# TSAL.net
KiCad netlist of a schematic drawn in EasyEDA Pro
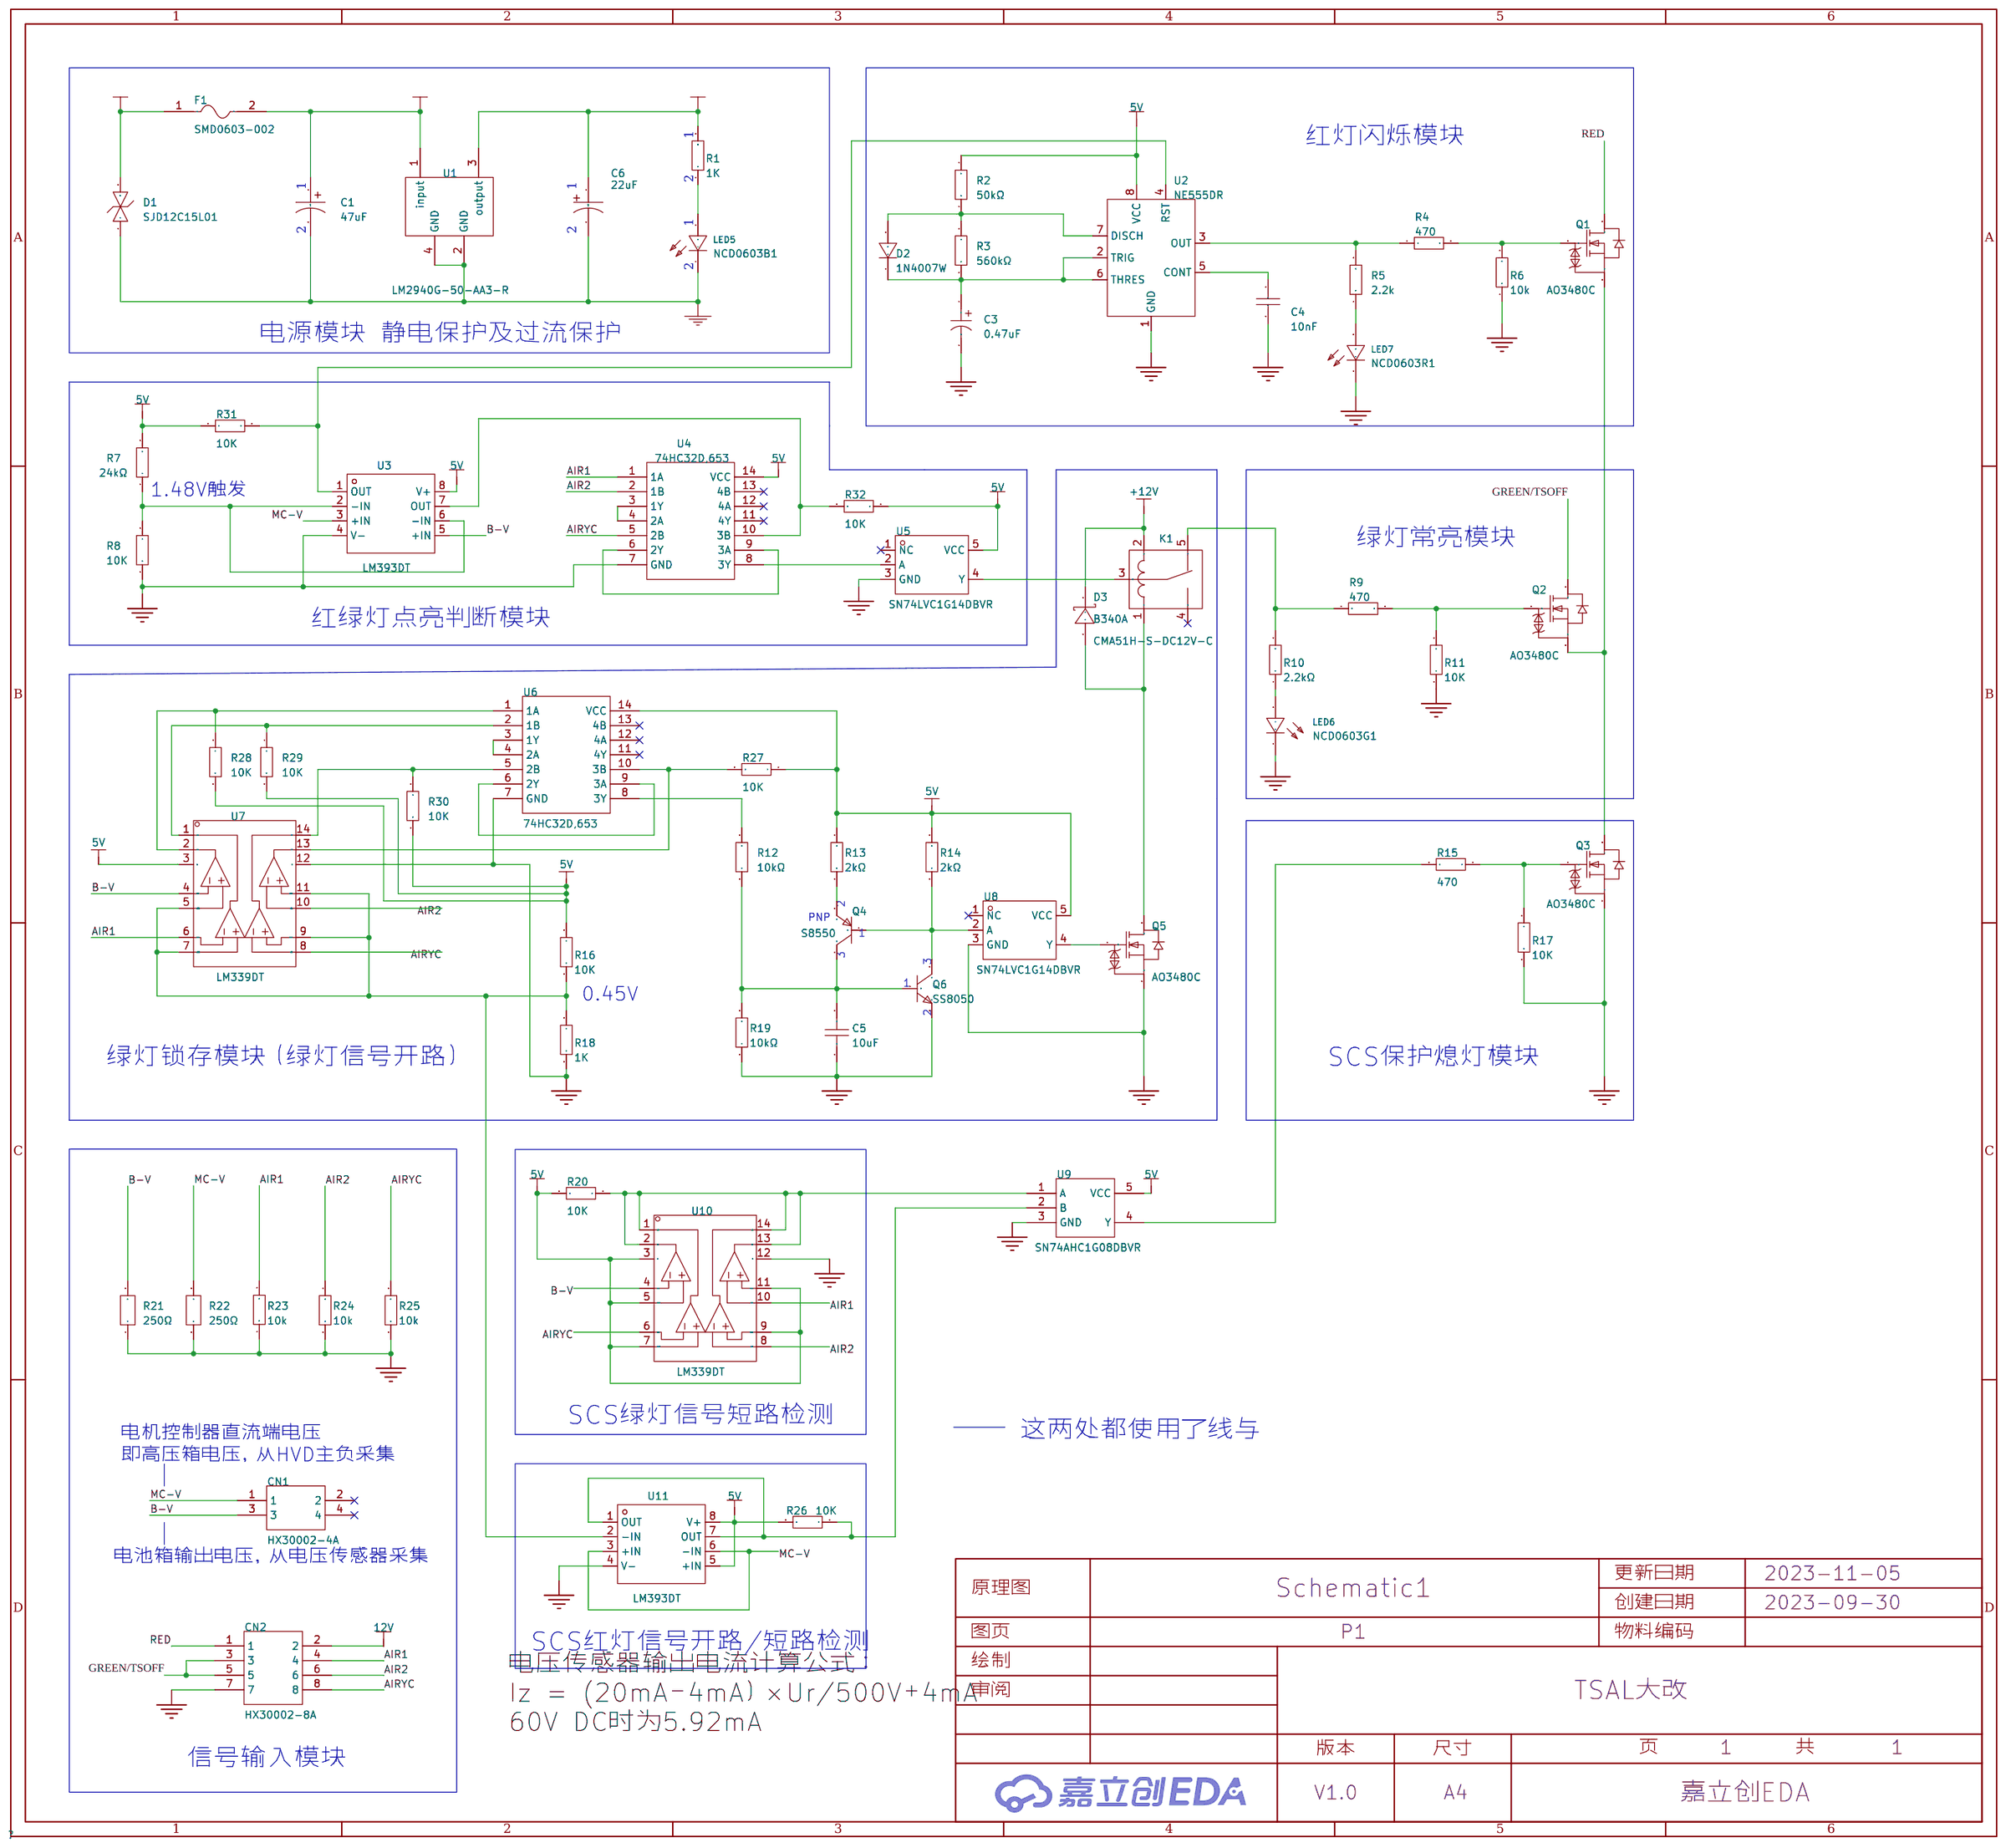
[diagram p0: schematic sheet]

(export (version "E")
  (design (tool "Eeschema 10.0.6"))
  (components
    (comp (ref "C1")
      (value "47uF")
      (footprint "easyedapro:CAP-SMD_BD8.0-L8.3-W8.3-FD")
      (description "容值:47uF;精度:±20%;额定电压:63V;")
      (fields (field (name "Manufacturer Part") "HBW470M1JTR-0810") (field (name "Manufacturer") "lelon(立隆)"))
      (libsource (lib "easyedapro") (part "HBW470M1JTR-0810"))
    )
    (comp (ref "C3")
      (value "0.47uF")
      (footprint "easyedapro:CAP-SMD_L3.2-W1.6-FD-1")
      (description "容值:470nF;精度:±10%;额定电压:35V;")
      (fields
        (field (name "Manufacturer Part") "CA45A-A-35V-0.47UF-K")
        (field (name "Manufacturer") "CEC(振华新云)")
      )
      (libsource (lib "easyedapro") (part "CA45A-A-35V-0.47UF-K"))
    )
    (comp (ref "C4")
      (value "10nF")
      (footprint "easyedapro:C0603")
      (description "容值:10nF;精度:±10%;额定电压:50V;材质(温度系数):X7R;")
      (fields (field (name "Manufacturer Part") "0603B103K500NT") (field (name "Manufacturer") "FH(风华)"))
      (libsource (lib "easyedapro") (part "0603B103K500NT"))
    )
    (comp (ref "C5")
      (value "10uF")
      (fields
        (field (name "Manufacturer Part") "CL10A106KP8NNNC")
        (field (name "Manufacturer") "SAMSUNG(三星)")
      )
      (libsource (lib "easyedapro") (part "cl10a106ma8nrnc"))
    )
    (comp (ref "C6")
      (value "22uF")
      (footprint "easyedapro:CAP-SMD_BD6.3-L6.6-W6.6-FD")
      (fields (field (name "Manufacturer Part") "EEHZA1J220XP") (field (name "Manufacturer") "PANASONIC(松下)"))
      (libsource (lib "easyedapro") (part "EEHZA1J220XP"))
    )
    (comp (ref "CN1")
      (value "HX30002-4A")
      (footprint "easyedapro:CONN-TH_30002-4A-T1P")
      (description "参考系列:-;间距:3mm;插针结构:2x2P;排数:2;每排PIN数:2;行距:3mm;安装方式:-;触头材质:黄铜;")
      (fields (field (name "Manufacturer") "HX(红星)"))
      (libsource (lib "easyedapro") (part "30002-4A-T1P"))
    )
    (comp (ref "CN2")
      (value "HX30002-8A")
      (footprint "easyedapro:CONN-TH_30002-8A-T1P")
      (description "参考系列:-;间距:3mm;插针结构:2x4P;排数:2;每排PIN数:4;行距:3mm;安装方式:-;触头材质:黄铜;")
      (fields (field (name "Manufacturer") "HX(红星)"))
      (libsource (lib "easyedapro") (part "30002-8A-T1P"))
    )
    (comp (ref "D1")
      (value "SJD12C15L01")
      (footprint "easyedapro:SOD-123_L2.7-W1.6-LS3.7-BI")
      (description "反向截止电压(Vrwm):15V;击穿电压(VBR):16.7V;峰值脉冲电流(Ipp)@8/20us:8.2A;钳位电压(Vc)@Ipp:24.4V;")
      (fields (field (name "Manufacturer") "Brightking(君耀电子)"))
      (libsource (lib "easyedapro") (part "SJD12C15L01"))
    )
    (comp (ref "D2")
      (value "1N4007W")
      (footprint "easyedapro:SOD-123_L2.8-W1.8-LS3.7-RD")
      (description "二极管配置:独立式;直流反向耐压(Vr):1kV;平均整流电流(Io):1A;正向压降(Vf):1.1V@1A;反向电流(Ir):5uA@1kV;")
      (fields (field (name "Manufacturer") "BLUE ROCKET(蓝箭)"))
      (libsource (lib "easyedapro") (part "1N4007W_C328592"))
    )
    (comp (ref "D3")
      (value "B340A")
      (footprint "easyedapro:SMA_L4.3-W2.6-LS5.1-RD")
      (description "直流反向耐压(Vr):40V;平均整流电流(Io):3A;正向压降(Vf):550mV@3A;")
      (fields (field (name "Manufacturer") "MDD"))
      (libsource (lib "easyedapro") (part "B340A"))
    )
    (comp (ref "F1")
      (value "SMD0603-002")
      (footprint "easyedapro:F0603")
      (description "30V,0.02A")
      (fields (field (name "Manufacturer") "台湾陆海"))
      (libsource (lib "easyedapro") (part "SMD0603-002"))
    )
    (comp (ref "K1")
      (value "CMA51H-S-DC12V-C")
      (footprint "easyedapro:RELAY-TH_CMA51H-S-DCXX-C")
      (description "引脚数:5;线圈电压:12V;触点形式:一组转换:1C(单刀双掷-转换);触点容量(电阻负载):15A@14VDC;触点材料:银合金;")
      (fields (field (name "Manufacturer") "HKE(汇港)"))
      (libsource (lib "easyedapro") (part "CMA51H-S-DC12V-C"))
    )
    (comp (ref "LED5")
      (value "NCD0603B1")
      (footprint "easyedapro:LED0603-RD")
      (description "发光颜色:蓝灯;")
      (fields (field (name "Manufacturer") "国星光电"))
      (libsource (lib "easyedapro") (part "FC-DA1608BK-470H10"))
    )
    (comp (ref "LED6")
      (value "NCD0603G1")
      (footprint "easyedapro:LED0603-RD")
      (description "发光颜色:翠绿;")
      (fields (field (name "Manufacturer") "国星光电"))
      (libsource (lib "easyedapro") (part "FC-D1608UGK-520D10"))
    )
    (comp (ref "LED7")
      (value "NCD0603R1")
      (footprint "easyedapro:LED0603-RD_RED")
      (description "发光颜色:红灯;")
      (fields (field (name "Manufacturer") "国星光电"))
      (libsource (lib "easyedapro") (part "FC-DA1608HRK-620D"))
    )
    (comp (ref "Q1")
      (value "AO3480C")
      (footprint "easyedapro:SOT-23-3_L2.9-W1.6-P1.90-LS2.8-BR")
      (fields (field (name "Manufacturer") "AOS"))
      (libsource (lib "easyedapro") (part "AO3480C"))
    )
    (comp (ref "Q2")
      (value "AO3480C")
      (footprint "easyedapro:SOT-23-3_L2.9-W1.6-P1.90-LS2.8-BR")
      (fields (field (name "Manufacturer") "AOS"))
      (libsource (lib "easyedapro") (part "AO3480C"))
    )
    (comp (ref "Q3")
      (value "AO3480C")
      (footprint "easyedapro:SOT-23-3_L2.9-W1.6-P1.90-LS2.8-BR")
      (fields (field (name "Manufacturer") "AOS"))
      (libsource (lib "easyedapro") (part "AO3480C"))
    )
    (comp (ref "Q4")
      (value "S8550")
      (fields (field (name "Manufacturer") "CJ(江苏长电/长晶)"))
      (libsource (lib "easyedapro") (part "pnp"))
    )
    (comp (ref "Q5")
      (value "AO3480C")
      (footprint "easyedapro:SOT-23-3_L2.9-W1.6-P1.90-LS2.8-BR")
      (fields (field (name "Manufacturer") "AOS"))
      (libsource (lib "easyedapro") (part "AO3480C"))
    )
    (comp (ref "Q6")
      (value "SS8050")
      (footprint "easyedapro:SOT-23-3_L2.9-W1.3-P1.90-LS2.4-BR")
      (description "晶体管类型:NPN;集射极击穿电压(Vceo):25V;集电极电流(Ic):1.5A;功率(Pd):300mW;直流电流增益(hFE@Ic,Vce):200@100mA,1V;")
      (fields (field (name "Manufacturer") "CJ(江苏长电/长晶)"))
      (libsource (lib "easyedapro") (part "SS8050_C2150"))
    )
    (comp (ref "R1")
      (value "1K")
      (footprint "easyedapro:R0603")
      (description "电阻类型:厚膜电阻;阻值:680Ω;精度:±1%;功率:100mW;")
      (fields
        (field (name "Manufacturer Part") "0603WAF6800T5E")
        (field (name "Manufacturer") "UNI-ROYAL(厚声)")
      )
      (libsource (lib "easyedapro") (part "0603WAF6800T5E"))
    )
    (comp (ref "R2")
      (value "50kΩ")
      (footprint "easyedapro:R0603")
      (description "阻值:50kΩ;精度:±0.1%;功率:62.5mW;")
      (fields (field (name "Manufacturer Part") "AR03BTC5002A") (field (name "Manufacturer") "Viking(光颉)"))
      (libsource (lib "easyedapro") (part "AR03BTC5002A"))
    )
    (comp (ref "R3")
      (value "560kΩ")
      (footprint "easyedapro:R0603")
      (description "电阻类型:厚膜电阻;阻值:560kΩ;精度:±1%;功率:100mW;")
      (fields
        (field (name "Manufacturer Part") "0603WAF5603T5E")
        (field (name "Manufacturer") "UNI-ROYAL(厚声)")
      )
      (libsource (lib "easyedapro") (part "0603WAF5603T5E"))
    )
    (comp (ref "R4")
      (value "470")
      (footprint "easyedapro:R0603")
      (description "电阻类型:厚膜电阻;阻值:470Ω;精度:±1%;功率:100mW;")
      (fields
        (field (name "Manufacturer Part") "0603WAF4700T5E")
        (field (name "Manufacturer") "UNI-ROYAL(厚声)")
      )
      (libsource (lib "easyedapro") (part "0603WAF4700T5E"))
    )
    (comp (ref "R5")
      (value "2.2k")
      (footprint "easyedapro:R0603")
      (description "电阻类型:厚膜电阻;阻值:2.2kΩ;精度:±1%;功率:100mW;")
      (fields
        (field (name "Manufacturer Part") "0603WAF2201T5E")
        (field (name "Manufacturer") "UNI-ROYAL(厚声)")
      )
      (libsource (lib "easyedapro") (part "0603WAF2201T5E"))
    )
    (comp (ref "R6")
      (value "10k")
      (footprint "easyedapro:R0603")
      (description "电阻类型:厚膜电阻;阻值:10kΩ;精度:±1%;功率:100mW;")
      (fields
        (field (name "Manufacturer Part") "0603WAF1002T5E")
        (field (name "Manufacturer") "UNI-ROYAL(厚声)")
      )
      (libsource (lib "easyedapro") (part "0603WAF1002T5E"))
    )
    (comp (ref "R7")
      (value "24kΩ")
      (footprint "easyedapro:R0603")
      (description "电阻类型:厚膜电阻;阻值:24kΩ;精度:±1%;功率:100mW;")
      (fields
        (field (name "Manufacturer Part") "0603WAF2402T5E")
        (field (name "Manufacturer") "UNI-ROYAL(厚声)")
      )
      (libsource (lib "easyedapro") (part "0603WAF2402T5E"))
    )
    (comp (ref "R8") (value "10K") (footprint "easyedapro:R0603") (libsource (lib "easyedapro") (part "电阻")))
    (comp (ref "R9")
      (value "470")
      (footprint "easyedapro:R0603")
      (description "电阻类型:厚膜电阻;阻值:470Ω;精度:±1%;功率:100mW;")
      (fields
        (field (name "Manufacturer Part") "0603WAF4700T5E")
        (field (name "Manufacturer") "UNI-ROYAL(厚声)")
      )
      (libsource (lib "easyedapro") (part "0603WAF4700T5E"))
    )
    (comp (ref "R10")
      (value "2.2kΩ")
      (footprint "easyedapro:R0603")
      (description "电阻类型:厚膜电阻;阻值:2.2kΩ;精度:±1%;功率:100mW;")
      (fields
        (field (name "Manufacturer Part") "0603WAF2201T5E")
        (field (name "Manufacturer") "UNI-ROYAL(厚声)")
      )
      (libsource (lib "easyedapro") (part "0603WAF2201T5E"))
    )
    (comp (ref "R11") (value "10K") (footprint "easyedapro:R0603") (libsource (lib "easyedapro") (part "电阻")))
    (comp (ref "R12")
      (value "10kΩ")
      (footprint "easyedapro:R0603")
      (fields
        (field (name "Manufacturer Part") "0603WAF1002T5E")
        (field (name "Manufacturer") "UNI-ROYAL(厚声)")
      )
      (libsource (lib "easyedapro") (part "电阻"))
    )
    (comp (ref "R13")
      (value "2kΩ")
      (footprint "easyedapro:R0603")
      (description "电阻类型:厚膜电阻;阻值:2kΩ;精度:±1%;功率:100mW;")
      (fields
        (field (name "Manufacturer Part") "0603WAF2001T5E")
        (field (name "Manufacturer") "UNI-ROYAL(厚声)")
      )
      (libsource (lib "easyedapro") (part "0603WAF2001T5E"))
    )
    (comp (ref "R14")
      (value "2kΩ")
      (footprint "easyedapro:R0603")
      (description "电阻类型:厚膜电阻;阻值:2kΩ;精度:±1%;功率:100mW;")
      (fields
        (field (name "Manufacturer Part") "0603WAF2001T5E")
        (field (name "Manufacturer") "UNI-ROYAL(厚声)")
      )
      (libsource (lib "easyedapro") (part "0603WAF2001T5E"))
    )
    (comp (ref "R15")
      (value "470")
      (footprint "easyedapro:R0603")
      (description "电阻类型:厚膜电阻;阻值:470Ω;精度:±1%;功率:100mW;")
      (fields
        (field (name "Manufacturer Part") "0603WAF4700T5E")
        (field (name "Manufacturer") "UNI-ROYAL(厚声)")
      )
      (libsource (lib "easyedapro") (part "0603WAF4700T5E"))
    )
    (comp (ref "R16") (value "10K") (footprint "easyedapro:R0603") (libsource (lib "easyedapro") (part "电阻")))
    (comp (ref "R17") (value "10K") (footprint "easyedapro:R0603") (libsource (lib "easyedapro") (part "电阻")))
    (comp (ref "R18")
      (value "1K")
      (footprint "easyedapro:R0603")
      (description "电阻类型:厚膜电阻;阻值:680Ω;精度:±1%;功率:100mW;")
      (fields
        (field (name "Manufacturer Part") "0603WAF6800T5E")
        (field (name "Manufacturer") "UNI-ROYAL(厚声)")
      )
      (libsource (lib "easyedapro") (part "0603WAF6800T5E"))
    )
    (comp (ref "R19")
      (value "10kΩ")
      (footprint "easyedapro:R0603")
      (fields
        (field (name "Manufacturer Part") "0603WAF1002T5E")
        (field (name "Manufacturer") "UNI-ROYAL(厚声)")
      )
      (libsource (lib "easyedapro") (part "电阻"))
    )
    (comp (ref "R20") (value "10K") (footprint "easyedapro:R0603") (libsource (lib "easyedapro") (part "电阻")))
    (comp (ref "R21")
      (value "250Ω")
      (footprint "easyedapro:R0603")
      (description "电阻类型:薄膜电阻;阻值:250Ω;精度:±0.5%;功率:100mW;")
      (fields (field (name "Manufacturer Part") "ARG03DTC2500") (field (name "Manufacturer") "Viking(光颉)"))
      (libsource (lib "easyedapro") (part "ARG03DTC2500"))
    )
    (comp (ref "R22")
      (value "250Ω")
      (footprint "easyedapro:R0603")
      (description "电阻类型:薄膜电阻;阻值:250Ω;精度:±0.5%;功率:100mW;")
      (fields (field (name "Manufacturer Part") "ARG03DTC2500") (field (name "Manufacturer") "Viking(光颉)"))
      (libsource (lib "easyedapro") (part "ARG03DTC2500"))
    )
    (comp (ref "R23")
      (value "10k")
      (footprint "easyedapro:R0603")
      (description "电阻类型:厚膜电阻;阻值:10kΩ;精度:±1%;功率:100mW;")
      (fields
        (field (name "Manufacturer Part") "0603WAF1002T5E")
        (field (name "Manufacturer") "UNI-ROYAL(厚声)")
      )
      (libsource (lib "easyedapro") (part "0603WAF1002T5E"))
    )
    (comp (ref "R24")
      (value "10k")
      (footprint "easyedapro:R0603")
      (description "电阻类型:厚膜电阻;阻值:10kΩ;精度:±1%;功率:100mW;")
      (fields
        (field (name "Manufacturer Part") "0603WAF1002T5E")
        (field (name "Manufacturer") "UNI-ROYAL(厚声)")
      )
      (libsource (lib "easyedapro") (part "0603WAF1002T5E"))
    )
    (comp (ref "R25")
      (value "10k")
      (footprint "easyedapro:R0603")
      (description "电阻类型:厚膜电阻;阻值:10kΩ;精度:±1%;功率:100mW;")
      (fields
        (field (name "Manufacturer Part") "0603WAF1002T5E")
        (field (name "Manufacturer") "UNI-ROYAL(厚声)")
      )
      (libsource (lib "easyedapro") (part "0603WAF1002T5E"))
    )
    (comp (ref "R26") (value "10K") (footprint "easyedapro:R0603") (libsource (lib "easyedapro") (part "电阻")))
    (comp (ref "R27") (value "10K") (footprint "easyedapro:R0603") (libsource (lib "easyedapro") (part "电阻")))
    (comp (ref "R28") (value "10K") (footprint "easyedapro:R0603") (libsource (lib "easyedapro") (part "电阻")))
    (comp (ref "R29") (value "10K") (footprint "easyedapro:R0603") (libsource (lib "easyedapro") (part "电阻")))
    (comp (ref "R30") (value "10K") (footprint "easyedapro:R0603") (libsource (lib "easyedapro") (part "电阻")))
    (comp (ref "R31") (value "10K") (footprint "easyedapro:R0603") (libsource (lib "easyedapro") (part "电阻")))
    (comp (ref "R32") (value "10K") (footprint "easyedapro:R0603") (libsource (lib "easyedapro") (part "电阻")))
    (comp (ref "U1")
      (value "LM2940G-50-AA3-R")
      (footprint "easyedapro:SOT-223-4_L6.5-W3.5-P2.30-LS7.0-BR")
      (description "输出类型:固定;输出极性:正;输出通道数:1;最大输入电压:26V;输出电压:5V;压差:800mV@(1A);输出电流:1A;电源纹波抑制比(PSRR):72dB@(120Hz);")
      (fields (field (name "Manufacturer") "UTC(友顺)"))
      (libsource (lib "easyedapro") (part "LM2940G-50-AA3-R"))
    )
    (comp (ref "U2")
      (value "NE555DR")
      (footprint "easyedapro:SOIC-8_L4.9-W3.9-P1.27-LS6.0-BL")
      (description "类型:555 型，计时器/振荡器(单路);计数:-;工作电压:4.5V~16V;工作电流:10mA;工作温度:0°C~+70°C;")
      (fields (field (name "Manufacturer") "TI(德州仪器)"))
      (libsource (lib "easyedapro") (part "NE555DR"))
    )
    (comp (ref "U3")
      (value "LM393DT")
      (footprint "easyedapro:SOIC-8_L5.0-W4.0-P1.27-LS6.0-BL")
      (description "比较器组数:2;电源电压:2V~36V,±1V~18V;各通道供电电流:2.5mA;输出类型:CMOS, MOS, Open-Collector, TTL;传播延迟:-;")
      (fields (field (name "Manufacturer") "ST(意法半导体)"))
      (libsource (lib "easyedapro") (part "LM393DT"))
    )
    (comp (ref "U4")
      (value "74HC32D,653")
      (footprint "easyedapro:SOIC-14_L8.7-W3.9-P1.27-LS6.0-BL")
      (description "逻辑电路的归属系列:74HC;逻辑类型:或门;通道数:4;每通道输入数:2;电源电压:2V~6V;静态电流(最大值):2uA;")
      (fields (field (name "Manufacturer") "Nexperia(安世)"))
      (libsource (lib "easyedapro") (part "74HC32D,653"))
    )
    (comp (ref "U5")
      (value "SN74LVC1G14DBVR")
      (footprint "easyedapro:SOT-23-5_L3.0-W1.7-P0.95-LS2.8-BR")
      (description "逻辑电路的归属系列:-;逻辑类型:-;电路/元件数:-;输入数/每元件位数:-;电源电压:-;静态电流（最大值）:-;")
      (fields (field (name "Manufacturer") "UMW(广东友台半导体)"))
      (libsource (lib "easyedapro") (part "SN74LVC1G14DBVR_C434069"))
    )
    (comp (ref "U6")
      (value "74HC32D,653")
      (footprint "easyedapro:SOIC-14_L8.7-W3.9-P1.27-LS6.0-BL")
      (description "逻辑电路的归属系列:74HC;逻辑类型:或门;通道数:4;每通道输入数:2;电源电压:2V~6V;静态电流(最大值):2uA;")
      (fields (field (name "Manufacturer") "Nexperia(安世)"))
      (libsource (lib "easyedapro") (part "74HC32D,653"))
    )
    (comp (ref "U7")
      (value "LM339DT")
      (footprint "easyedapro:SOIC-14_L8.7-W3.9-P1.27-LS6.0-BL")
      (fields (field (name "Manufacturer") "ST(意法半导体)"))
      (libsource (lib "easyedapro") (part "LM339DT"))
    )
    (comp (ref "U8")
      (value "SN74LVC1G14DBVR")
      (footprint "easyedapro:SOT-23-5_L3.0-W1.7-P0.95-LS2.8-BR")
      (description "逻辑电路的归属系列:-;逻辑类型:-;电路/元件数:-;输入数/每元件位数:-;电源电压:-;静态电流（最大值）:-;")
      (fields (field (name "Manufacturer") "UMW(广东友台半导体)"))
      (libsource (lib "easyedapro") (part "SN74LVC1G14DBVR_C434069"))
    )
    (comp (ref "U9")
      (value "SN74AHC1G08DBVR")
      (footprint "easyedapro:SOT-23-5_L3.0-W1.7-P0.95-LS2.8-BR")
      (description "逻辑电路的归属系列:74AHC;逻辑类型:与门;通道数:1;每通道输入数:2;电源电压:2V~5.5V;静态电流(最大值):1uA;")
      (fields (field (name "Manufacturer") "TI(德州仪器)"))
      (libsource (lib "easyedapro") (part "SN74AHC1G08DBVRG4"))
    )
    (comp (ref "U10")
      (value "LM339DT")
      (footprint "easyedapro:SOIC-14_L8.7-W3.9-P1.27-LS6.0-BL")
      (fields (field (name "Manufacturer") "ST(意法半导体)"))
      (libsource (lib "easyedapro") (part "LM339DT"))
    )
    (comp (ref "U11")
      (value "LM393DT")
      (footprint "easyedapro:SOIC-8_L5.0-W4.0-P1.27-LS6.0-BL")
      (description "比较器组数:2;电源电压:2V~36V,±1V~18V;各通道供电电流:2.5mA;输出类型:CMOS, MOS, Open-Collector, TTL;传播延迟:-;")
      (fields (field (name "Manufacturer") "ST(意法半导体)"))
      (libsource (lib "easyedapro") (part "LM393DT"))
    )
  )
  (nets
    (net (code "1") (name "+12V") (class "Default")
      (node (ref "C1") (pin "1") (pinfunction "1_1") (pintype "input"))
      (node (ref "D3") (pin "1") (pinfunction "K_1") (pintype "input"))
      (node (ref "F1") (pin "2") (pinfunction "2_2") (pintype "input"))
      (node (ref "K1") (pin "2") (pinfunction "2_2") (pintype "input"))
      (node (ref "U1") (pin "1") (pinfunction "input_1") (pintype "input"))
    )
    (net (code "2") (name "/AIR1") (class "Default")
      (node (ref "CN2") (pin "4") (pinfunction "4_4") (pintype "input"))
      (node (ref "R23") (pin "2") (pinfunction "2_2") (pintype "input"))
      (node (ref "U10") (pin "10") (pinfunction "Inverting_input4_10") (pintype "input"))
      (node (ref "U4") (pin "1") (pinfunction "1A_1") (pintype "input"))
      (node (ref "U7") (pin "6") (pinfunction "Inverting_input2_6") (pintype "input"))
    )
    (net (code "3") (name "/AIR2") (class "Default")
      (node (ref "CN2") (pin "6") (pinfunction "6_6") (pintype "input"))
      (node (ref "R24") (pin "2") (pinfunction "2_2") (pintype "input"))
      (node (ref "U10") (pin "8") (pinfunction "Inverting_input3_8") (pintype "input"))
      (node (ref "U4") (pin "2") (pinfunction "1B_2") (pintype "input"))
      (node (ref "U7") (pin "10") (pinfunction "Inverting_input4_10") (pintype "input"))
    )
    (net (code "4") (name "/AIRYC") (class "Default")
      (node (ref "CN2") (pin "8") (pinfunction "8_8") (pintype "input"))
      (node (ref "R25") (pin "2") (pinfunction "2_2") (pintype "input"))
      (node (ref "U10") (pin "6") (pinfunction "Inverting_input2_6") (pintype "input"))
      (node (ref "U4") (pin "5") (pinfunction "2B_5") (pintype "input"))
      (node (ref "U7") (pin "8") (pinfunction "Inverting_input3_8") (pintype "input"))
    )
    (net (code "5") (name "/B-V") (class "Default")
      (node (ref "CN1") (pin "3") (pinfunction "3_3") (pintype "input"))
      (node (ref "R21") (pin "2") (pinfunction "2_2") (pintype "input"))
      (node (ref "U10") (pin "4") (pinfunction "Inverting_input1_4") (pintype "input"))
      (node (ref "U3") (pin "5") (pinfunction "+IN_5") (pintype "input"))
      (node (ref "U7") (pin "4") (pinfunction "Inverting_input1_4") (pintype "input"))
    )
    (net (code "6") (name "/GREEN{slash}TSOFF") (class "Default")
      (node (ref "CN2") (pin "3") (pinfunction "3_3") (pintype "input"))
      (node (ref "CN2") (pin "5") (pinfunction "5_5") (pintype "input"))
      (node (ref "Q2") (pin "3") (pinfunction "D_3") (pintype "input"))
    )
    (net (code "7") (name "/MC-V") (class "Default")
      (node (ref "CN1") (pin "1") (pinfunction "1_1") (pintype "input"))
      (node (ref "R22") (pin "2") (pinfunction "2_2") (pintype "input"))
      (node (ref "U11") (pin "3") (pinfunction "+IN_3") (pintype "input"))
      (node (ref "U11") (pin "6") (pinfunction "-IN_6") (pintype "input"))
      (node (ref "U3") (pin "3") (pinfunction "+IN_3") (pintype "input"))
    )
    (net (code "8") (name "/RED") (class "Default")
      (node (ref "CN2") (pin "1") (pinfunction "1_1") (pintype "input"))
      (node (ref "Q1") (pin "3") (pinfunction "D_3") (pintype "input"))
    )
    (net (code "9") (name "5V") (class "Default")
      (node (ref "C6") (pin "1") (pinfunction "1_1") (pintype "input"))
      (node (ref "R1") (pin "2") (pinfunction "2_2") (pintype "input"))
      (node (ref "R13") (pin "2") (pinfunction "2_2") (pintype "input"))
      (node (ref "R14") (pin "2") (pinfunction "2_2") (pintype "input"))
      (node (ref "R16") (pin "2") (pinfunction "2_2") (pintype "input"))
      (node (ref "R2") (pin "2") (pinfunction "2_2") (pintype "input"))
      (node (ref "R20") (pin "2") (pinfunction "2_2") (pintype "input"))
      (node (ref "R26") (pin "2") (pinfunction "2_2") (pintype "input"))
      (node (ref "R27") (pin "1") (pinfunction "1_1") (pintype "input"))
      (node (ref "R28") (pin "2") (pinfunction "2_2") (pintype "input"))
      (node (ref "R29") (pin "2") (pinfunction "2_2") (pintype "input"))
      (node (ref "R30") (pin "2") (pinfunction "2_2") (pintype "input"))
      (node (ref "R31") (pin "1") (pinfunction "1_1") (pintype "input"))
      (node (ref "R32") (pin "2") (pinfunction "2_2") (pintype "input"))
      (node (ref "R7") (pin "2") (pinfunction "2_2") (pintype "input"))
      (node (ref "U1") (pin "3") (pinfunction "output_3") (pintype "input"))
      (node (ref "U10") (pin "11") (pinfunction "Non-inverting_input4_11") (pintype "input"))
      (node (ref "U10") (pin "3") (pinfunction "VDD_3") (pintype "input"))
      (node (ref "U10") (pin "5") (pinfunction "Non-inverting_input1_5") (pintype "input"))
      (node (ref "U10") (pin "7") (pinfunction "Non-inverting_input2_7") (pintype "input"))
      (node (ref "U10") (pin "9") (pinfunction "Non-inverting_input3_9") (pintype "input"))
      (node (ref "U11") (pin "5") (pinfunction "+IN_5") (pintype "input"))
      (node (ref "U11") (pin "8") (pinfunction "V+_8") (pintype "input"))
      (node (ref "U2") (pin "8") (pinfunction "VCC_8") (pintype "input"))
      (node (ref "U3") (pin "8") (pinfunction "V+_8") (pintype "input"))
      (node (ref "U4") (pin "14") (pinfunction "VCC_14") (pintype "input"))
      (node (ref "U5") (pin "5") (pinfunction "VCC_5") (pintype "input"))
      (node (ref "U6") (pin "14") (pinfunction "VCC_14") (pintype "input"))
      (node (ref "U7") (pin "3") (pinfunction "VDD_3") (pintype "input"))
      (node (ref "U8") (pin "5") (pinfunction "VCC_5") (pintype "input"))
      (node (ref "U9") (pin "5") (pinfunction "VCC_5") (pintype "input"))
    )
    (net (code "10") (name "12V") (class "Default")
      (node (ref "CN2") (pin "2") (pinfunction "2_2") (pintype "input"))
      (node (ref "D1") (pin "2") (pinfunction "2_2") (pintype "input"))
      (node (ref "F1") (pin "1") (pinfunction "1_1") (pintype "input"))
    )
    (net (code "11") (name "GND") (class "Default")
      (node (ref "C1") (pin "2") (pinfunction "2_2") (pintype "input"))
      (node (ref "C3") (pin "2") (pinfunction "2_2") (pintype "input"))
      (node (ref "C4") (pin "2") (pinfunction "2_2") (pintype "input"))
      (node (ref "C5") (pin "2") (pinfunction "2_2") (pintype "input"))
      (node (ref "C6") (pin "2") (pinfunction "2_2") (pintype "input"))
      (node (ref "CN2") (pin "7") (pinfunction "7_7") (pintype "input"))
      (node (ref "D1") (pin "1") (pinfunction "1_1") (pintype "input"))
      (node (ref "LED5") (pin "1") (pinfunction "-_1") (pintype "input"))
      (node (ref "LED6") (pin "1") (pinfunction "K_1") (pintype "input"))
      (node (ref "LED7") (pin "1") (pinfunction "K_1") (pintype "input"))
      (node (ref "Q3") (pin "2") (pinfunction "S_2") (pintype "input"))
      (node (ref "Q5") (pin "2") (pinfunction "S_2") (pintype "input"))
      (node (ref "Q6") (pin "2") (pinfunction "E_2") (pintype "input"))
      (node (ref "R11") (pin "1") (pinfunction "1_1") (pintype "input"))
      (node (ref "R17") (pin "1") (pinfunction "1_1") (pintype "input"))
      (node (ref "R18") (pin "1") (pinfunction "1_1") (pintype "input"))
      (node (ref "R19") (pin "1") (pinfunction "1_1") (pintype "input"))
      (node (ref "R21") (pin "1") (pinfunction "1_1") (pintype "input"))
      (node (ref "R22") (pin "1") (pinfunction "1_1") (pintype "input"))
      (node (ref "R23") (pin "1") (pinfunction "1_1") (pintype "input"))
      (node (ref "R24") (pin "1") (pinfunction "1_1") (pintype "input"))
      (node (ref "R25") (pin "1") (pinfunction "1_1") (pintype "input"))
      (node (ref "R6") (pin "1") (pinfunction "1_1") (pintype "input"))
      (node (ref "R8") (pin "1") (pinfunction "1_1") (pintype "input"))
      (node (ref "U1") (pin "2") (pinfunction "GND_2") (pintype "input"))
      (node (ref "U1") (pin "4") (pinfunction "GND_4") (pintype "input"))
      (node (ref "U10") (pin "12") (pinfunction "GND_12") (pintype "input"))
      (node (ref "U11") (pin "4") (pinfunction "V-_4") (pintype "input"))
      (node (ref "U2") (pin "1") (pinfunction "GND_1") (pintype "input"))
      (node (ref "U3") (pin "4") (pinfunction "V-_4") (pintype "input"))
      (node (ref "U4") (pin "7") (pinfunction "GND_7") (pintype "input"))
      (node (ref "U5") (pin "3") (pinfunction "GND_3") (pintype "input"))
      (node (ref "U6") (pin "7") (pinfunction "GND_7") (pintype "input"))
      (node (ref "U7") (pin "12") (pinfunction "GND_12") (pintype "input"))
      (node (ref "U8") (pin "3") (pinfunction "GND_3") (pintype "input"))
      (node (ref "U9") (pin "3") (pinfunction "GND_3") (pintype "input"))
    )
    (net (code "12") (name "Net-(D3-A)") (class "Default")
      (node (ref "D3") (pin "2") (pinfunction "A_2") (pintype "input"))
      (node (ref "K1") (pin "1") (pinfunction "1_1") (pintype "input"))
      (node (ref "Q5") (pin "3") (pinfunction "D_3") (pintype "input"))
    )
    (net (code "13") (name "Net-(K1-Pad5)") (class "Default")
      (node (ref "K1") (pin "5") (pinfunction "5_5") (pintype "input"))
      (node (ref "R10") (pin "2") (pinfunction "2_2") (pintype "input"))
      (node (ref "R9") (pin "2") (pinfunction "2_2") (pintype "input"))
    )
    (net (code "14") (name "Net-(LED5-+)") (class "Default")
      (node (ref "LED5") (pin "2") (pinfunction "+_2") (pintype "input"))
      (node (ref "R1") (pin "1") (pinfunction "1_1") (pintype "input"))
    )
    (net (code "15") (name "Net-(LED6-A)") (class "Default")
      (node (ref "LED6") (pin "2") (pinfunction "A_2") (pintype "input"))
      (node (ref "R10") (pin "1") (pinfunction "1_1") (pintype "input"))
    )
    (net (code "16") (name "Net-(LED7-A)") (class "Default")
      (node (ref "LED7") (pin "2") (pinfunction "A_2") (pintype "input"))
      (node (ref "R5") (pin "1") (pinfunction "1_1") (pintype "input"))
    )
    (net (code "17") (name "Net-(Q1-G)") (class "Default")
      (node (ref "Q1") (pin "1") (pinfunction "G_1") (pintype "input"))
      (node (ref "R4") (pin "2") (pinfunction "2_2") (pintype "input"))
      (node (ref "R6") (pin "2") (pinfunction "2_2") (pintype "input"))
    )
    (net (code "18") (name "Net-(Q1-S)") (class "Default")
      (node (ref "Q1") (pin "2") (pinfunction "S_2") (pintype "input"))
      (node (ref "Q2") (pin "2") (pinfunction "S_2") (pintype "input"))
      (node (ref "Q3") (pin "3") (pinfunction "D_3") (pintype "input"))
    )
    (net (code "19") (name "Net-(Q2-G)") (class "Default")
      (node (ref "Q2") (pin "1") (pinfunction "G_1") (pintype "input"))
      (node (ref "R11") (pin "2") (pinfunction "2_2") (pintype "input"))
      (node (ref "R9") (pin "1") (pinfunction "1_1") (pintype "input"))
    )
    (net (code "20") (name "Net-(Q3-G)") (class "Default")
      (node (ref "Q3") (pin "1") (pinfunction "G_1") (pintype "input"))
      (node (ref "R15") (pin "1") (pinfunction "1_1") (pintype "input"))
      (node (ref "R17") (pin "2") (pinfunction "2_2") (pintype "input"))
    )
    (net (code "21") (name "Net-(Q4-B)") (class "Default")
      (node (ref "Q4") (pin "1") (pinfunction "B_1") (pintype "input"))
      (node (ref "Q6") (pin "3") (pinfunction "C_3") (pintype "input"))
      (node (ref "R14") (pin "1") (pinfunction "1_1") (pintype "input"))
      (node (ref "U8") (pin "2") (pinfunction "A_2") (pintype "input"))
    )
    (net (code "22") (name "Net-(Q4-C)") (class "Default")
      (node (ref "C5") (pin "1") (pinfunction "1_1") (pintype "input"))
      (node (ref "Q4") (pin "3") (pinfunction "C_3") (pintype "input"))
      (node (ref "Q6") (pin "1") (pinfunction "B_1") (pintype "input"))
      (node (ref "R12") (pin "1") (pinfunction "1_1") (pintype "input"))
      (node (ref "R19") (pin "2") (pinfunction "2_2") (pintype "input"))
    )
    (net (code "23") (name "Net-(Q4-E)") (class "Default")
      (node (ref "Q4") (pin "2") (pinfunction "E_2") (pintype "input"))
      (node (ref "R13") (pin "1") (pinfunction "1_1") (pintype "input"))
    )
    (net (code "24") (name "Net-(Q5-G)") (class "Default")
      (node (ref "Q5") (pin "1") (pinfunction "G_1") (pintype "input"))
      (node (ref "U8") (pin "4") (pinfunction "Y_4") (pintype "input"))
    )
    (net (code "25") (name "Net-(R7-Pad1)") (class "Default")
      (node (ref "R7") (pin "1") (pinfunction "1_1") (pintype "input"))
      (node (ref "R8") (pin "2") (pinfunction "2_2") (pintype "input"))
      (node (ref "U3") (pin "2") (pinfunction "-IN_2") (pintype "input"))
      (node (ref "U3") (pin "6") (pinfunction "-IN_6") (pintype "input"))
    )
    (net (code "26") (name "Net-(U2-CONT)") (class "Default")
      (node (ref "C4") (pin "1") (pinfunction "1_1") (pintype "input"))
      (node (ref "U2") (pin "5") (pinfunction "CONT_5") (pintype "input"))
    )
    (net (code "27") (name "Net-(U2-DISCH)") (class "Default")
      (node (ref "D2") (pin "2") (pinfunction "2_2") (pintype "input"))
      (node (ref "R2") (pin "1") (pinfunction "1_1") (pintype "input"))
      (node (ref "R3") (pin "2") (pinfunction "2_2") (pintype "input"))
      (node (ref "U2") (pin "7") (pinfunction "DISCH_7") (pintype "input"))
    )
    (net (code "28") (name "Net-(U2-OUT)") (class "Default")
      (node (ref "R4") (pin "1") (pinfunction "1_1") (pintype "input"))
      (node (ref "R5") (pin "2") (pinfunction "2_2") (pintype "input"))
      (node (ref "U2") (pin "3") (pinfunction "OUT_3") (pintype "input"))
    )
    (net (code "29") (name "Net-(U2-RST)") (class "Default")
      (node (ref "R31") (pin "2") (pinfunction "2_2") (pintype "input"))
      (node (ref "U2") (pin "4") (pinfunction "RST_4") (pintype "input"))
      (node (ref "U3") (pin "1") (pinfunction "OUT_1") (pintype "input"))
    )
    (net (code "30") (name "Net-(U2-THRES)") (class "Default")
      (node (ref "C3") (pin "1") (pinfunction "1_1") (pintype "input"))
      (node (ref "D2") (pin "1") (pinfunction "1_1") (pintype "input"))
      (node (ref "R3") (pin "1") (pinfunction "1_1") (pintype "input"))
      (node (ref "U2") (pin "2") (pinfunction "TRIG_2") (pintype "input"))
      (node (ref "U2") (pin "6") (pinfunction "THRES_6") (pintype "input"))
    )
    (net (code "31") (name "Net-(U4-1Y)") (class "Default")
      (node (ref "U4") (pin "3") (pinfunction "1Y_3") (pintype "input"))
      (node (ref "U4") (pin "4") (pinfunction "2A_4") (pintype "input"))
    )
    (net (code "32") (name "Net-(U4-2Y)") (class "Default")
      (node (ref "U4") (pin "6") (pinfunction "2Y_6") (pintype "input"))
      (node (ref "U4") (pin "9") (pinfunction "3A_9") (pintype "input"))
    )
    (net (code "33") (name "Net-(U4-3B)") (class "Default")
      (node (ref "R32") (pin "1") (pinfunction "1_1") (pintype "input"))
      (node (ref "U3") (pin "7") (pinfunction "OUT_7") (pintype "input"))
      (node (ref "U4") (pin "10") (pinfunction "3B_10") (pintype "input"))
    )
    (net (code "34") (name "Net-(U4-3Y)") (class "Default")
      (node (ref "U4") (pin "8") (pinfunction "3Y_8") (pintype "input"))
      (node (ref "U5") (pin "2") (pinfunction "A_2") (pintype "input"))
    )
    (net (code "35") (name "Net-(U5-Y)") (class "Default")
      (node (ref "K1") (pin "3") (pinfunction "3_3") (pintype "input"))
      (node (ref "U5") (pin "4") (pinfunction "Y_4") (pintype "input"))
    )
    (net (code "36") (name "Net-(U6-1A)") (class "Default")
      (node (ref "R28") (pin "1") (pinfunction "1_1") (pintype "input"))
      (node (ref "U6") (pin "1") (pinfunction "1A_1") (pintype "input"))
      (node (ref "U7") (pin "2") (pinfunction "OUTPUT1_2") (pintype "input"))
    )
    (net (code "37") (name "Net-(U6-1B)") (class "Default")
      (node (ref "R29") (pin "1") (pinfunction "1_1") (pintype "input"))
      (node (ref "U6") (pin "2") (pinfunction "1B_2") (pintype "input"))
      (node (ref "U7") (pin "1") (pinfunction "OUTPUT2_1") (pintype "input"))
    )
    (net (code "38") (name "Net-(U6-1Y)") (class "Default")
      (node (ref "U6") (pin "3") (pinfunction "1Y_3") (pintype "input"))
      (node (ref "U6") (pin "4") (pinfunction "2A_4") (pintype "input"))
    )
    (net (code "39") (name "Net-(U6-2B)") (class "Default")
      (node (ref "R30") (pin "1") (pinfunction "1_1") (pintype "input"))
      (node (ref "U6") (pin "5") (pinfunction "2B_5") (pintype "input"))
      (node (ref "U7") (pin "14") (pinfunction "OUTPUT3_14") (pintype "input"))
    )
    (net (code "40") (name "Net-(U6-2Y)") (class "Default")
      (node (ref "U6") (pin "6") (pinfunction "2Y_6") (pintype "input"))
      (node (ref "U6") (pin "9") (pinfunction "3A_9") (pintype "input"))
    )
    (net (code "41") (name "Net-(U6-3B)") (class "Default")
      (node (ref "R27") (pin "2") (pinfunction "2_2") (pintype "input"))
      (node (ref "U6") (pin "10") (pinfunction "3B_10") (pintype "input"))
      (node (ref "U7") (pin "13") (pinfunction "OUTPUT4_13") (pintype "input"))
    )
    (net (code "42") (name "Net-(U6-3Y)") (class "Default")
      (node (ref "R12") (pin "2") (pinfunction "2_2") (pintype "input"))
      (node (ref "U6") (pin "8") (pinfunction "3Y_8") (pintype "input"))
    )
    (net (code "43") (name "Net-(U7-Non-inverting_input1)") (class "Default")
      (node (ref "R16") (pin "1") (pinfunction "1_1") (pintype "input"))
      (node (ref "R18") (pin "2") (pinfunction "2_2") (pintype "input"))
      (node (ref "U11") (pin "2") (pinfunction "-IN_2") (pintype "input"))
      (node (ref "U7") (pin "11") (pinfunction "Non-inverting_input4_11") (pintype "input"))
      (node (ref "U7") (pin "5") (pinfunction "Non-inverting_input1_5") (pintype "input"))
      (node (ref "U7") (pin "7") (pinfunction "Non-inverting_input2_7") (pintype "input"))
      (node (ref "U7") (pin "9") (pinfunction "Non-inverting_input3_9") (pintype "input"))
    )
    (net (code "44") (name "Net-(U9-B)") (class "Default")
      (node (ref "R26") (pin "1") (pinfunction "1_1") (pintype "input"))
      (node (ref "U11") (pin "1") (pinfunction "OUT_1") (pintype "input"))
      (node (ref "U11") (pin "7") (pinfunction "OUT_7") (pintype "input"))
      (node (ref "U9") (pin "2") (pinfunction "B_2") (pintype "input"))
    )
    (net (code "45") (name "Net-(U9-Y)") (class "Default")
      (node (ref "R15") (pin "2") (pinfunction "2_2") (pintype "input"))
      (node (ref "U9") (pin "4") (pinfunction "Y_4") (pintype "input"))
    )
    (net (code "46") (name "Net-(U10-OUTPUT1)") (class "Default")
      (node (ref "R20") (pin "1") (pinfunction "1_1") (pintype "input"))
      (node (ref "U10") (pin "1") (pinfunction "OUTPUT2_1") (pintype "input"))
      (node (ref "U10") (pin "13") (pinfunction "OUTPUT4_13") (pintype "input"))
      (node (ref "U10") (pin "14") (pinfunction "OUTPUT3_14") (pintype "input"))
      (node (ref "U10") (pin "2") (pinfunction "OUTPUT1_2") (pintype "input"))
      (node (ref "U9") (pin "1") (pinfunction "A_1") (pintype "input"))
    )
    (net (code "47") (name "unconnected-(CN1-Pad2)") (class "Default")
      (node (ref "CN1") (pin "2") (pinfunction "2_2") (pintype "input+no_connect"))
    )
    (net (code "48") (name "unconnected-(CN1-Pad4)") (class "Default")
      (node (ref "CN1") (pin "4") (pinfunction "4_4") (pintype "input+no_connect"))
    )
    (net (code "49") (name "unconnected-(K1-Pad4)") (class "Default")
      (node (ref "K1") (pin "4") (pinfunction "4_4") (pintype "input+no_connect"))
    )
    (net (code "50") (name "unconnected-(U4-4A-Pad12)") (class "Default")
      (node (ref "U4") (pin "12") (pinfunction "4A_12") (pintype "input+no_connect"))
    )
    (net (code "51") (name "unconnected-(U4-4B-Pad13)") (class "Default")
      (node (ref "U4") (pin "13") (pinfunction "4B_13") (pintype "input+no_connect"))
    )
    (net (code "52") (name "unconnected-(U4-4Y-Pad11)") (class "Default")
      (node (ref "U4") (pin "11") (pinfunction "4Y_11") (pintype "input+no_connect"))
    )
    (net (code "53") (name "unconnected-(U5-NC-Pad1)") (class "Default")
      (node (ref "U5") (pin "1") (pinfunction "NC_1") (pintype "input+no_connect"))
    )
    (net (code "54") (name "unconnected-(U6-4A-Pad12)") (class "Default")
      (node (ref "U6") (pin "12") (pinfunction "4A_12") (pintype "input+no_connect"))
    )
    (net (code "55") (name "unconnected-(U6-4B-Pad13)") (class "Default")
      (node (ref "U6") (pin "13") (pinfunction "4B_13") (pintype "input+no_connect"))
    )
    (net (code "56") (name "unconnected-(U6-4Y-Pad11)") (class "Default")
      (node (ref "U6") (pin "11") (pinfunction "4Y_11") (pintype "input+no_connect"))
    )
    (net (code "57") (name "unconnected-(U8-NC-Pad1)") (class "Default")
      (node (ref "U8") (pin "1") (pinfunction "NC_1") (pintype "input+no_connect"))
    )
  )
)
